# Analog_PDB_V1.net
KiCad netlist of a schematic drawn in EAGLE
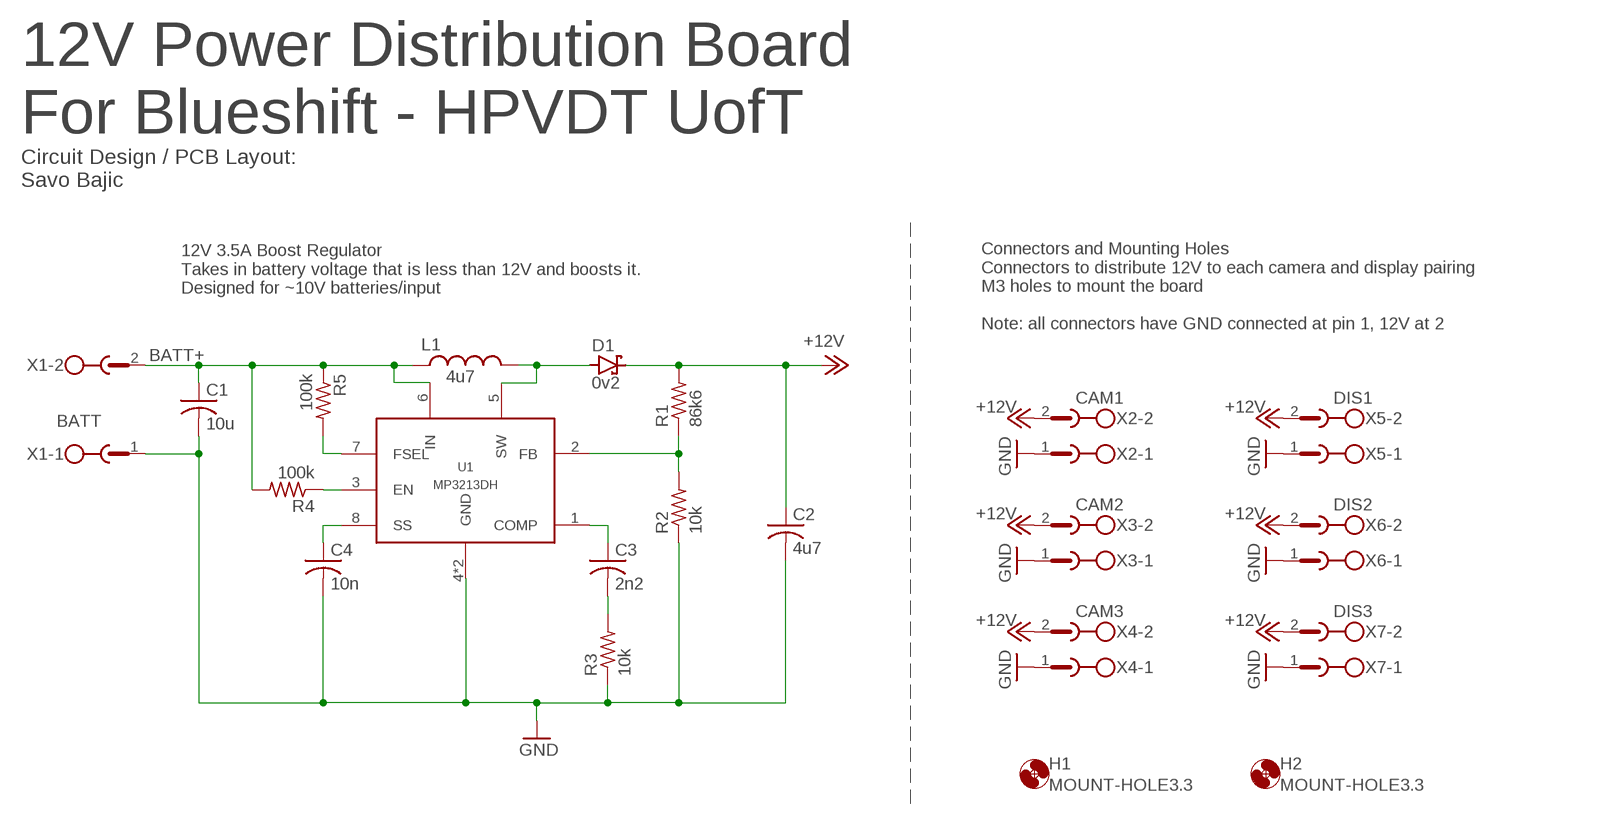
[diagram p0: schematic, sheet 1]

(export (version "E")
  (design (tool "Eeschema 10.0.6"))
  (components
    (comp (ref "C1")
      (value "10u")
      (footprint "eagle-import:C0603")
      (libsource (lib "eagle-import") (part "C-USC0603"))
    )
    (comp (ref "C2")
      (value "4u7")
      (footprint "eagle-import:C0603")
      (libsource (lib "eagle-import") (part "C-USC0603"))
    )
    (comp (ref "C3")
      (value "2n2")
      (footprint "eagle-import:C0603")
      (libsource (lib "eagle-import") (part "C-USC0603"))
    )
    (comp (ref "C4")
      (value "10n")
      (footprint "eagle-import:C0603")
      (libsource (lib "eagle-import") (part "C-USC0603"))
    )
    (comp (ref "D1")
      (value "0v2")
      (footprint "eagle-import:DO-214AB")
      (libsource (lib "eagle-import") (part "BOOSTDIODE"))
    )
    (comp (ref "H1")
      (value "MOUNT-HOLE3.3")
      (footprint "eagle-import:3,3")
      (libsource (lib "eagle-import") (part "MOUNT-HOLE3.3"))
    )
    (comp (ref "H2")
      (value "MOUNT-HOLE3.3")
      (footprint "eagle-import:3,3")
      (libsource (lib "eagle-import") (part "MOUNT-HOLE3.3"))
    )
    (comp (ref "L1")
      (value "4u7")
      (footprint "eagle-import:SDES053T")
      (libsource (lib "eagle-import") (part "SDEI054T"))
    )
    (comp (ref "R1")
      (value "86k6")
      (footprint "eagle-import:R0402")
      (libsource (lib "eagle-import") (part "R-US_R0402"))
    )
    (comp (ref "R2")
      (value "10k")
      (footprint "eagle-import:R0402")
      (libsource (lib "eagle-import") (part "R-US_R0402"))
    )
    (comp (ref "R3")
      (value "10k")
      (footprint "eagle-import:R0402")
      (libsource (lib "eagle-import") (part "R-US_R0402"))
    )
    (comp (ref "R4")
      (value "100k")
      (footprint "eagle-import:R0402")
      (libsource (lib "eagle-import") (part "R-US_R0402"))
    )
    (comp (ref "R5")
      (value "100k")
      (footprint "eagle-import:R0402")
      (libsource (lib "eagle-import") (part "R-US_R0402"))
    )
    (comp (ref "U1")
      (value "MP3213DH")
      (footprint "eagle-import:8-TSSOP")
      (libsource (lib "eagle-import") (part "MP3213DH"))
    )
    (comp (ref "X1")
      (value "BATT")
      (footprint "eagle-import:MSTBV2")
      (libsource (lib "eagle-import") (part "MST2V"))
    )
    (comp (ref "X2")
      (value "CAM1")
      (footprint "eagle-import:MSTBV2")
      (fields (field (name "MPN") "MSTBV 2,5/2-GF-5.08"))
      (libsource (lib "eagle-import") (part "MSTBV2"))
    )
    (comp (ref "X3")
      (value "CAM2")
      (footprint "eagle-import:MSTBV2")
      (fields (field (name "MPN") "MSTBV 2,5/2-GF-5.08"))
      (libsource (lib "eagle-import") (part "MSTBV2"))
    )
    (comp (ref "X4")
      (value "CAM3")
      (footprint "eagle-import:MSTBV2")
      (fields (field (name "MPN") "MSTBV 2,5/2-GF-5.08"))
      (libsource (lib "eagle-import") (part "MSTBV2"))
    )
    (comp (ref "X5")
      (value "DIS1")
      (footprint "eagle-import:MSTBV2")
      (fields (field (name "MPN") "MSTBV 2,5/2-GF-5.08"))
      (libsource (lib "eagle-import") (part "MSTBV2"))
    )
    (comp (ref "X6")
      (value "DIS2")
      (footprint "eagle-import:MSTBV2")
      (fields (field (name "MPN") "MSTBV 2,5/2-GF-5.08"))
      (libsource (lib "eagle-import") (part "MSTBV2"))
    )
    (comp (ref "X7")
      (value "DIS3")
      (footprint "eagle-import:MSTBV2")
      (fields (field (name "MPN") "MSTBV 2,5/2-GF-5.08"))
      (libsource (lib "eagle-import") (part "MSTBV2"))
    )
  )
  (nets
    (net (code "1") (name "+12V") (class "Default")
      (node (ref "C2") (pin "1") (pinfunction "1_1") (pintype "passive"))
      (node (ref "D1") (pin "C") (pinfunction "C_C") (pintype "passive"))
      (node (ref "R1") (pin "2") (pinfunction "2_2") (pintype "passive"))
      (node (ref "X2") (pin "2") (pinfunction "1_2") (pintype "passive"))
      (node (ref "X3") (pin "2") (pinfunction "1_2") (pintype "passive"))
      (node (ref "X4") (pin "2") (pinfunction "1_2") (pintype "passive"))
      (node (ref "X5") (pin "2") (pinfunction "1_2") (pintype "passive"))
      (node (ref "X6") (pin "2") (pinfunction "1_2") (pintype "passive"))
      (node (ref "X7") (pin "2") (pinfunction "1_2") (pintype "passive"))
    )
    (net (code "2") (name "/BATT+") (class "Default")
      (node (ref "C1") (pin "1") (pinfunction "1_1") (pintype "passive"))
      (node (ref "L1") (pin "1") (pinfunction "1_1") (pintype "passive"))
      (node (ref "R4") (pin "2") (pinfunction "2_2") (pintype "passive"))
      (node (ref "R5") (pin "1") (pinfunction "1_1") (pintype "passive"))
      (node (ref "U1") (pin "6") (pinfunction "IN_6") (pintype "bidirectional"))
      (node (ref "X1") (pin "2") (pinfunction "1_2") (pintype "passive"))
    )
    (net (code "3") (name "GND") (class "Default")
      (node (ref "C1") (pin "2") (pinfunction "2_2") (pintype "passive"))
      (node (ref "C2") (pin "2") (pinfunction "2_2") (pintype "passive"))
      (node (ref "C4") (pin "2") (pinfunction "2_2") (pintype "passive"))
      (node (ref "R2") (pin "1") (pinfunction "1_1") (pintype "passive"))
      (node (ref "R3") (pin "1") (pinfunction "1_1") (pintype "passive"))
      (node (ref "U1") (pin "4") (pinfunction "GND_4") (pintype "bidirectional"))
      (node (ref "U1") (pin "P") (pinfunction "GND_P") (pintype "bidirectional"))
      (node (ref "X1") (pin "1") (pinfunction "1_1") (pintype "passive"))
      (node (ref "X2") (pin "1") (pinfunction "1_1") (pintype "passive"))
      (node (ref "X3") (pin "1") (pinfunction "1_1") (pintype "passive"))
      (node (ref "X4") (pin "1") (pinfunction "1_1") (pintype "passive"))
      (node (ref "X5") (pin "1") (pinfunction "1_1") (pintype "passive"))
      (node (ref "X6") (pin "1") (pinfunction "1_1") (pintype "passive"))
      (node (ref "X7") (pin "1") (pinfunction "1_1") (pintype "passive"))
    )
    (net (code "4") (name "Net-(C3-Pad2)") (class "Default")
      (node (ref "C3") (pin "2") (pinfunction "2_2") (pintype "passive"))
      (node (ref "R3") (pin "2") (pinfunction "2_2") (pintype "passive"))
    )
    (net (code "5") (name "Net-(U1-COMP)") (class "Default")
      (node (ref "C3") (pin "1") (pinfunction "1_1") (pintype "passive"))
      (node (ref "U1") (pin "1") (pinfunction "COMP_1") (pintype "bidirectional"))
    )
    (net (code "6") (name "Net-(U1-EN)") (class "Default")
      (node (ref "R4") (pin "1") (pinfunction "1_1") (pintype "passive"))
      (node (ref "U1") (pin "3") (pinfunction "EN_3") (pintype "bidirectional"))
    )
    (net (code "7") (name "Net-(U1-FB)") (class "Default")
      (node (ref "R1") (pin "1") (pinfunction "1_1") (pintype "passive"))
      (node (ref "R2") (pin "2") (pinfunction "2_2") (pintype "passive"))
      (node (ref "U1") (pin "2") (pinfunction "FB_2") (pintype "bidirectional"))
    )
    (net (code "8") (name "Net-(U1-FSEL)") (class "Default")
      (node (ref "R5") (pin "2") (pinfunction "2_2") (pintype "passive"))
      (node (ref "U1") (pin "7") (pinfunction "FSEL_7") (pintype "bidirectional"))
    )
    (net (code "9") (name "Net-(U1-SS)") (class "Default")
      (node (ref "C4") (pin "1") (pinfunction "1_1") (pintype "passive"))
      (node (ref "U1") (pin "8") (pinfunction "SS_8") (pintype "bidirectional"))
    )
    (net (code "10") (name "Net-(U1-SW)") (class "Default")
      (node (ref "D1") (pin "A") (pinfunction "A_A") (pintype "passive"))
      (node (ref "L1") (pin "2") (pinfunction "2_2") (pintype "passive"))
      (node (ref "U1") (pin "5") (pinfunction "SW_5") (pintype "bidirectional"))
    )
  )
)
